# Doorbell_2021-06-07.net
KiCad netlist of a schematic drawn in EasyEDA
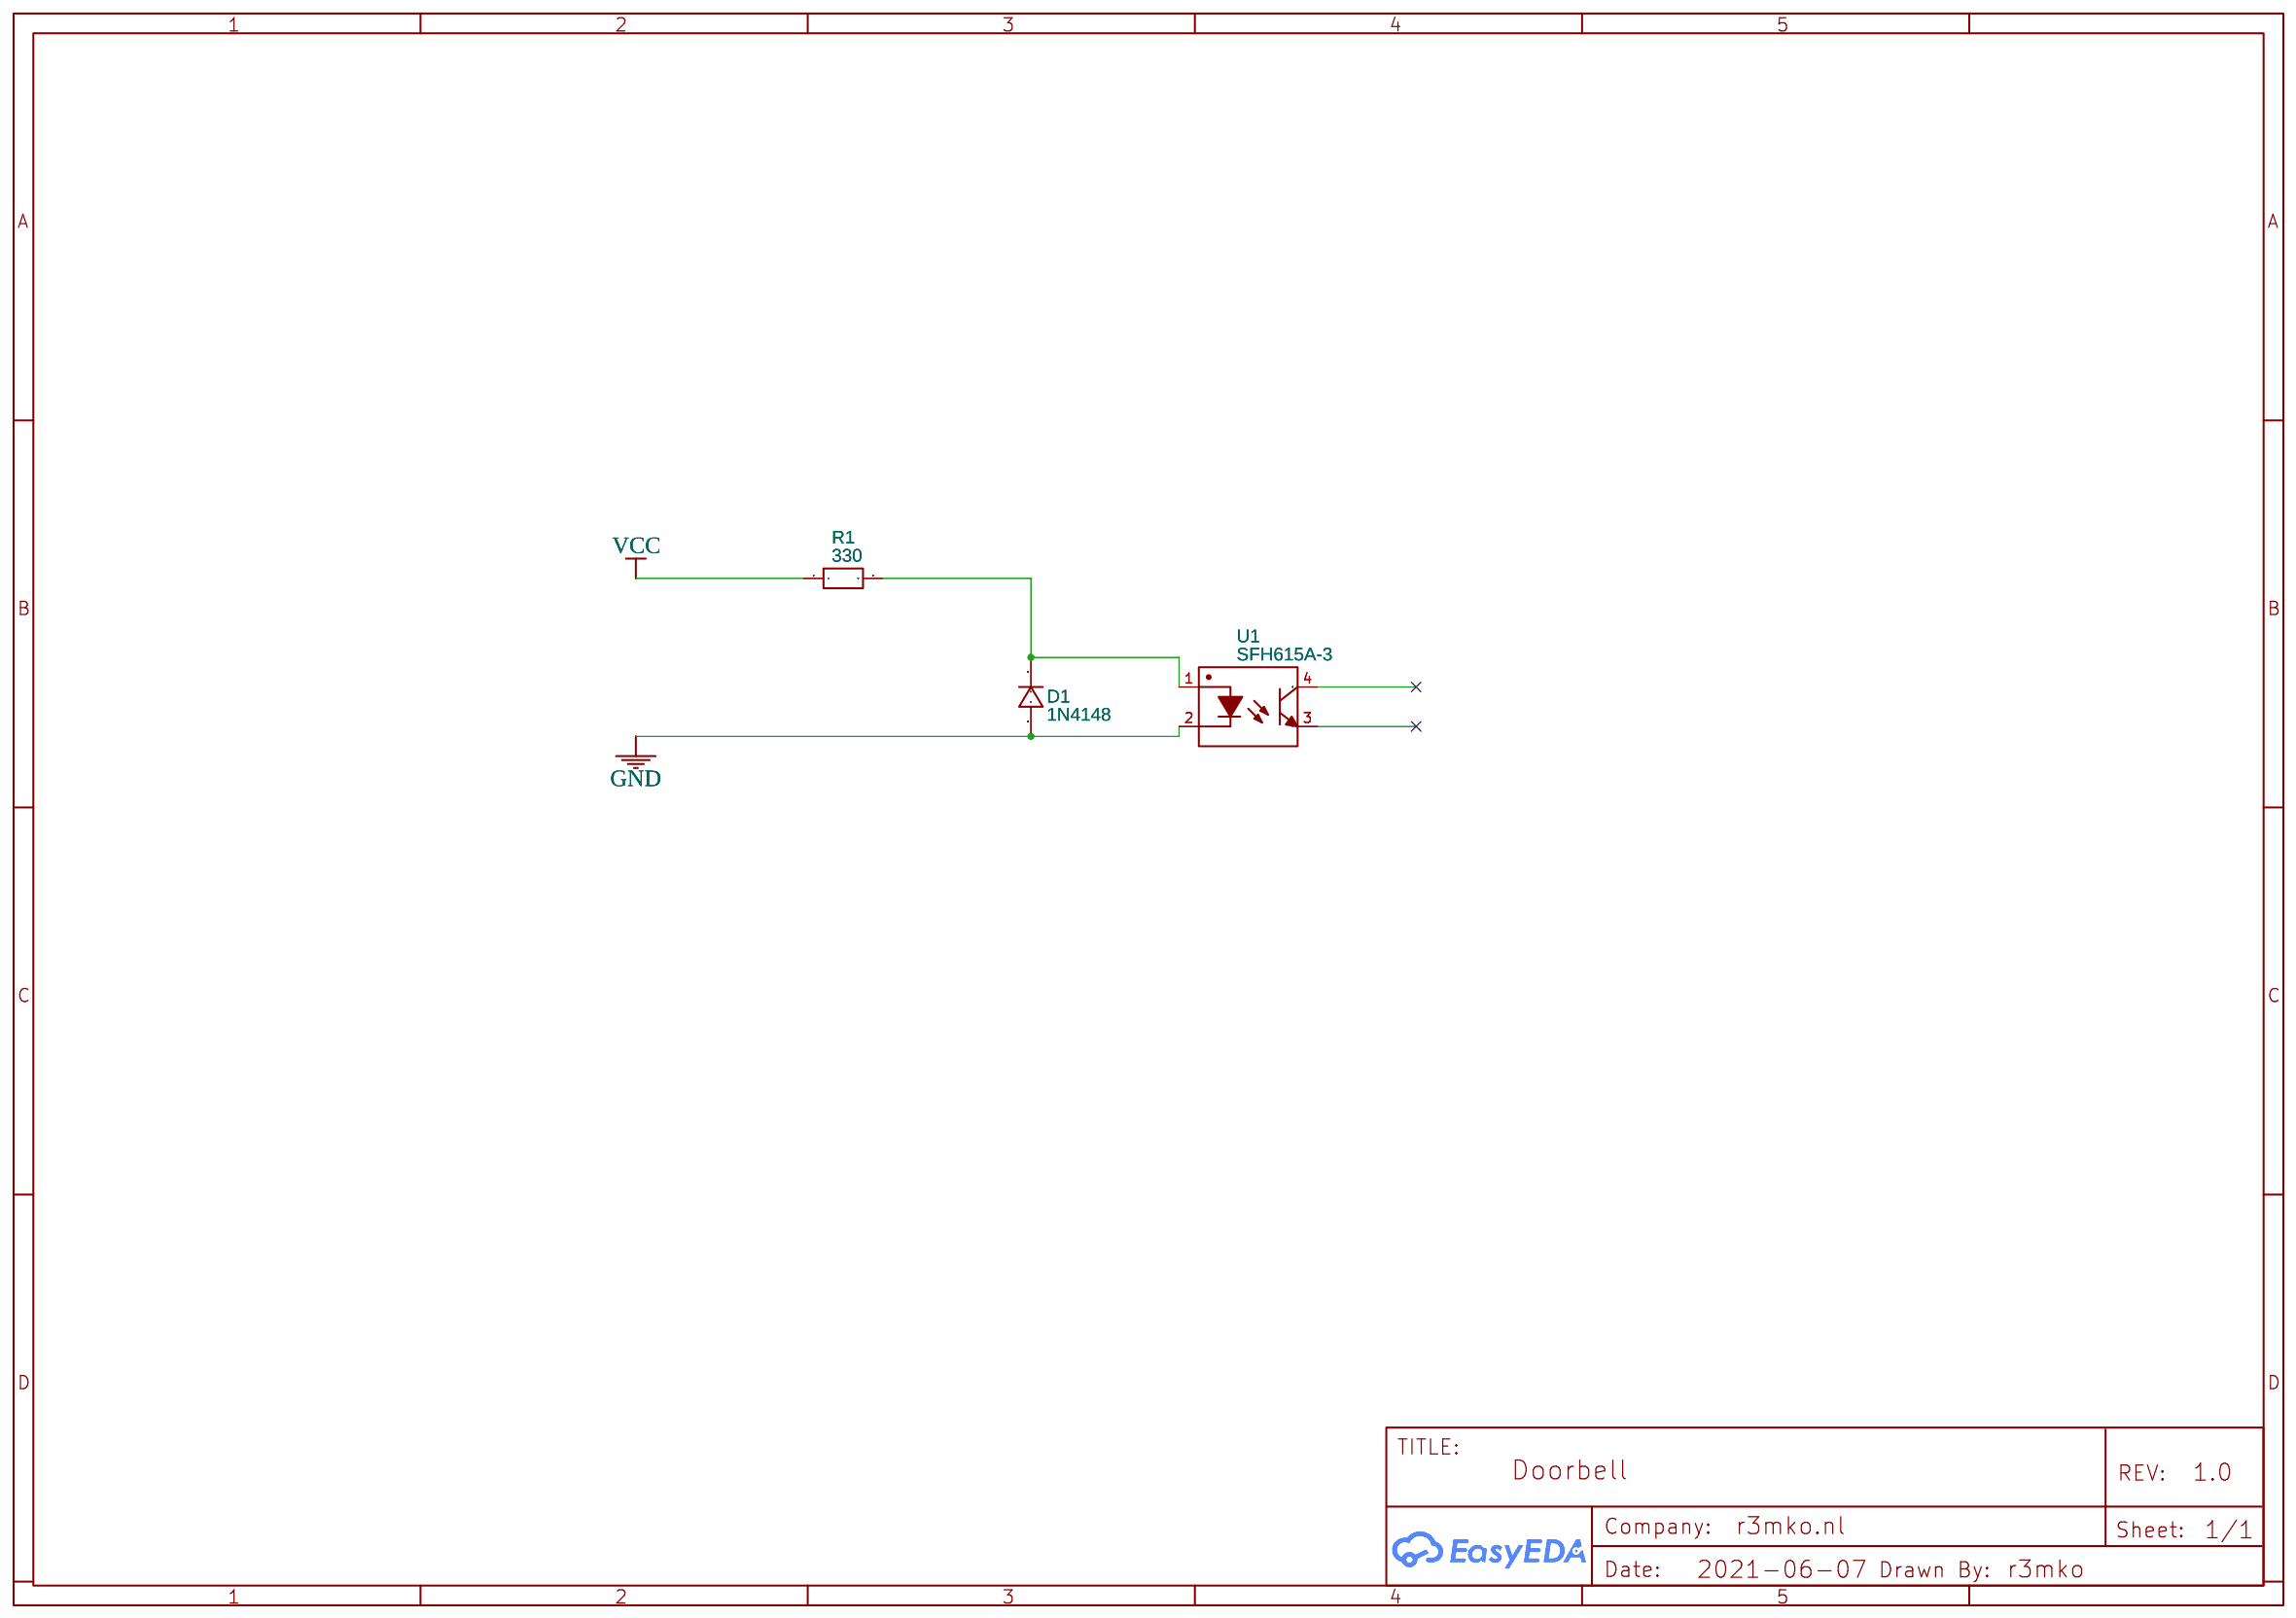
[diagram p0: schematic sheet]

(export (version "E")
  (design (tool "Eeschema 10.0.6"))
  (components
    (comp (ref "D1")
      (value "1N4148")
      (fields (field (name "BOM_Supplier Part") "C14516"))
      (libsource (lib "") (part "1N4148"))
    )
    (comp (ref "R1") (value "330") (libsource (lib "") (part "R_AXIAL-0.3_EU")))
    (comp (ref "U1")
      (value "SFH615A-3")
      (fields (field (name "BOM_Supplier Part") "C500641"))
      (libsource (lib "") (part "SFH615A-3"))
    )
  )
  (nets
    (net (code "1") (name "GND") (class "Default")
      (node (ref "D1") (pin "1") (pinfunction "1_1") (pintype "unspecified"))
      (node (ref "U1") (pin "2") (pinfunction "C_2") (pintype "unspecified"))
    )
    (net (code "2") (name "Net-(U1-A)") (class "Default")
      (node (ref "D1") (pin "2") (pinfunction "2_2") (pintype "unspecified"))
      (node (ref "R1") (pin "2") (pinfunction "2_2") (pintype "unspecified"))
      (node (ref "U1") (pin "1") (pinfunction "A_1") (pintype "unspecified"))
    )
    (net (code "3") (name "VCC") (class "Default")
      (node (ref "R1") (pin "1") (pinfunction "1_1") (pintype "unspecified"))
    )
    (net (code "4") (name "unconnected-(U1-C-Pad4)") (class "Default")
      (node (ref "U1") (pin "4") (pinfunction "C_4") (pintype "unspecified+no_connect"))
    )
    (net (code "5") (name "unconnected-(U1-E-Pad3)") (class "Default")
      (node (ref "U1") (pin "3") (pinfunction "E_3") (pintype "unspecified+no_connect"))
    )
  )
)
